# NTAG_I2C_plus_Class4_Antenna_v1.net
KiCad netlist of a schematic drawn in EAGLE
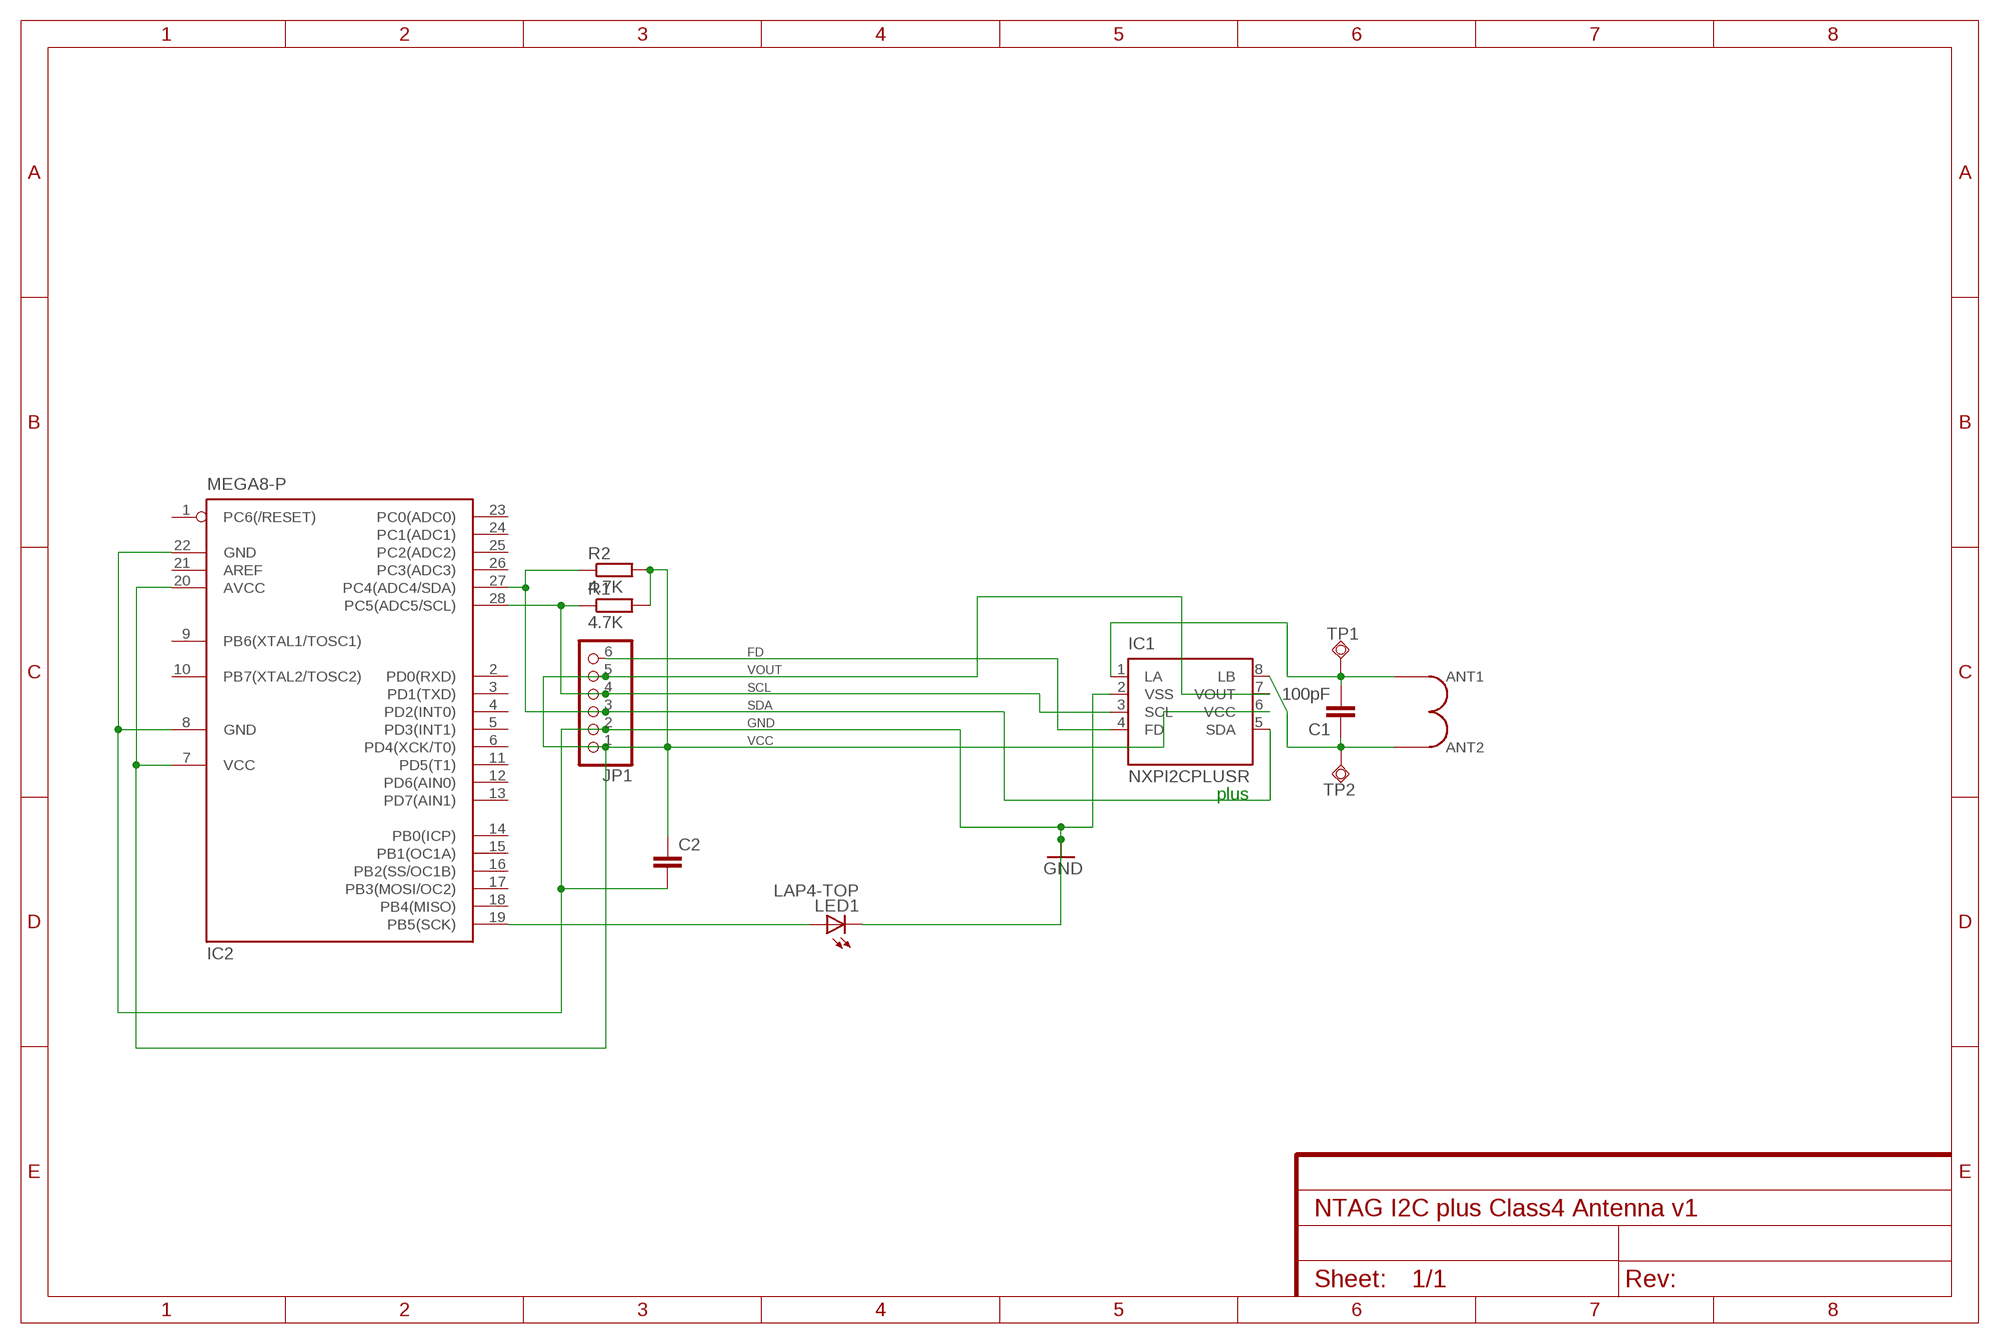
[diagram p0: schematic, sheet 1]

(export (version "E")
  (design (tool "Eeschema 10.0.6"))
  (components
    (comp (ref "C1")
      (value "100pF")
      (footprint "eagle-import:C0402K")
      (libsource (lib "eagle-import") (part "C-EUC0402K"))
    )
    (comp (ref "C2")
      (value "C-EU025-030X050")
      (footprint "eagle-import:C025-030X050")
      (libsource (lib "eagle-import") (part "rcl_334_C-EU025-030X050"))
    )
    (comp (ref "IC1")
      (value "NXPI2CPLUSR")
      (footprint "eagle-import:SO8")
      (fields (field (name "MPN") "AD780BRZ-REEL"))
      (libsource (lib "eagle-import") (part "NXPI2CPLUSR"))
    )
    (comp (ref "IC2")
      (value "MEGA8-P")
      (footprint "eagle-import:DIL28-3")
      (libsource (lib "eagle-import") (part "MEGA8-P"))
    )
    (comp (ref "JP1")
      (value "PINHD-1X6/90")
      (footprint "eagle-import:1X06_90")
      (libsource (lib "eagle-import") (part "PINHD-1X6/90"))
    )
    (comp (ref "LED1")
      (value "LAP4-TOP")
      (footprint "eagle-import:P47F-TOP")
      (libsource (lib "eagle-import") (part "P4-TOPLA"))
    )
    (comp (ref "R1")
      (value "4.7K")
      (footprint "eagle-import:0204_7")
      (libsource (lib "eagle-import") (part "R-EU_0204/7"))
    )
    (comp (ref "R2")
      (value "4.7K")
      (footprint "eagle-import:0204_7")
      (libsource (lib "eagle-import") (part "R-EU_0204/7"))
    )
    (comp (ref "TP1")
      (value "TPSQPAD1-13")
      (footprint "eagle-import:P1-13")
      (libsource (lib "eagle-import") (part "TPSQPAD1-13"))
    )
    (comp (ref "TP2")
      (value "TPSQPAD1-13")
      (footprint "eagle-import:P1-13")
      (libsource (lib "eagle-import") (part "TPSQPAD1-13"))
    )
    (comp (ref "U$1")
      (value "ENERGY-HARVESTING_3-TURNS54X27_3TURN_THIN")
      (footprint "eagle-import:54X27_3TURNS_THIN")
      (libsource (lib "eagle-import") (part "ENERGY-HARVESTING_3-TURNS54X27_3TURN_THIN"))
    )
  )
  (nets
    (net (code "1") (name "GND") (class "Default")
      (node (ref "C2") (pin "2") (pinfunction "2_2") (pintype "passive"))
      (node (ref "IC1") (pin "2") (pinfunction "VSS_2") (pintype "power_in"))
      (node (ref "IC2") (pin "22") (pinfunction "GND_22") (pintype "power_in"))
      (node (ref "IC2") (pin "8") (pinfunction "GND_8") (pintype "power_in"))
      (node (ref "JP1") (pin "2") (pinfunction "2_2") (pintype "passive"))
      (node (ref "LED1") (pin "C") (pinfunction "C_C") (pintype "passive"))
    )
    (net (code "2") (name "Net-(IC1-FD)") (class "Default")
      (node (ref "IC1") (pin "4") (pinfunction "FD_4") (pintype "bidirectional"))
      (node (ref "JP1") (pin "6") (pinfunction "6_6") (pintype "passive"))
    )
    (net (code "3") (name "Net-(IC1-LA)") (class "Default")
      (node (ref "C1") (pin "2") (pinfunction "2_2") (pintype "passive"))
      (node (ref "IC1") (pin "1") (pinfunction "LA_1") (pintype "bidirectional"))
      (node (ref "TP1") (pin "TP") (pinfunction "TP_TP") (pintype "input"))
      (node (ref "U$1") (pin "ANT1") (pinfunction "ANT1_ANT1") (pintype "bidirectional"))
    )
    (net (code "4") (name "Net-(IC1-LB)") (class "Default")
      (node (ref "C1") (pin "1") (pinfunction "1_1") (pintype "passive"))
      (node (ref "IC1") (pin "8") (pinfunction "LB_8") (pintype "bidirectional"))
      (node (ref "TP2") (pin "TP") (pinfunction "TP_TP") (pintype "input"))
      (node (ref "U$1") (pin "ANT2") (pinfunction "ANT2_ANT2") (pintype "bidirectional"))
    )
    (net (code "5") (name "Net-(IC1-SCL)") (class "Default")
      (node (ref "IC1") (pin "3") (pinfunction "SCL_3") (pintype "bidirectional"))
      (node (ref "IC2") (pin "28") (pinfunction "PC5(ADC5/SCL)_28") (pintype "bidirectional"))
      (node (ref "JP1") (pin "4") (pinfunction "4_4") (pintype "passive"))
      (node (ref "R1") (pin "1") (pinfunction "1_1") (pintype "passive"))
    )
    (net (code "6") (name "Net-(IC1-SDA)") (class "Default")
      (node (ref "IC1") (pin "5") (pinfunction "SDA_5") (pintype "bidirectional"))
      (node (ref "IC2") (pin "27") (pinfunction "PC4(ADC4/SDA)_27") (pintype "bidirectional"))
      (node (ref "JP1") (pin "3") (pinfunction "3_3") (pintype "passive"))
      (node (ref "R2") (pin "1") (pinfunction "1_1") (pintype "passive"))
    )
    (net (code "7") (name "Net-(IC1-VCC)") (class "Default")
      (node (ref "C2") (pin "1") (pinfunction "1_1") (pintype "passive"))
      (node (ref "IC1") (pin "6") (pinfunction "VCC_6") (pintype "power_in"))
      (node (ref "IC1") (pin "7") (pinfunction "VOUT_7") (pintype "power_in"))
      (node (ref "IC2") (pin "20") (pinfunction "AVCC_20") (pintype "power_in"))
      (node (ref "IC2") (pin "7") (pinfunction "VCC_7") (pintype "power_in"))
      (node (ref "JP1") (pin "1") (pinfunction "1_1") (pintype "passive"))
      (node (ref "JP1") (pin "5") (pinfunction "5_5") (pintype "passive"))
      (node (ref "R1") (pin "2") (pinfunction "2_2") (pintype "passive"))
      (node (ref "R2") (pin "2") (pinfunction "2_2") (pintype "passive"))
    )
    (net (code "8") (name "Net-(IC2-PB5(SCK))") (class "Default")
      (node (ref "IC2") (pin "19") (pinfunction "PB5(SCK)_19") (pintype "bidirectional"))
      (node (ref "LED1") (pin "A") (pinfunction "A_A") (pintype "passive"))
    )
    (net (code "9") (name "unconnected-(IC2-AREF-Pad21)") (class "Default")
      (node (ref "IC2") (pin "21") (pinfunction "AREF_21") (pintype "passive"))
    )
    (net (code "10") (name "unconnected-(IC2-PB0(ICP)-Pad14)") (class "Default")
      (node (ref "IC2") (pin "14") (pinfunction "PB0(ICP)_14") (pintype "bidirectional"))
    )
    (net (code "11") (name "unconnected-(IC2-PB1(OC1A)-Pad15)") (class "Default")
      (node (ref "IC2") (pin "15") (pinfunction "PB1(OC1A)_15") (pintype "bidirectional"))
    )
    (net (code "12") (name "unconnected-(IC2-PB2(SS{slash}OC1B)-Pad16)") (class "Default")
      (node (ref "IC2") (pin "16") (pinfunction "PB2(SS/OC1B)_16") (pintype "bidirectional"))
    )
    (net (code "13") (name "unconnected-(IC2-PB3(MOSI{slash}OC2)-Pad17)") (class "Default")
      (node (ref "IC2") (pin "17") (pinfunction "PB3(MOSI/OC2)_17") (pintype "bidirectional"))
    )
    (net (code "14") (name "unconnected-(IC2-PB4(MISO)-Pad18)") (class "Default")
      (node (ref "IC2") (pin "18") (pinfunction "PB4(MISO)_18") (pintype "bidirectional"))
    )
    (net (code "15") (name "unconnected-(IC2-PB6(XTAL1{slash}TOSC1)-Pad9)") (class "Default")
      (node (ref "IC2") (pin "9") (pinfunction "PB6(XTAL1/TOSC1)_9") (pintype "bidirectional"))
    )
    (net (code "16") (name "unconnected-(IC2-PB7(XTAL2{slash}TOSC2)-Pad10)") (class "Default")
      (node (ref "IC2") (pin "10") (pinfunction "PB7(XTAL2/TOSC2)_10") (pintype "bidirectional"))
    )
    (net (code "17") (name "unconnected-(IC2-PC0(ADC0)-Pad23)") (class "Default")
      (node (ref "IC2") (pin "23") (pinfunction "PC0(ADC0)_23") (pintype "bidirectional"))
    )
    (net (code "18") (name "unconnected-(IC2-PC1(ADC1)-Pad24)") (class "Default")
      (node (ref "IC2") (pin "24") (pinfunction "PC1(ADC1)_24") (pintype "bidirectional"))
    )
    (net (code "19") (name "unconnected-(IC2-PC2(ADC2)-Pad25)") (class "Default")
      (node (ref "IC2") (pin "25") (pinfunction "PC2(ADC2)_25") (pintype "bidirectional"))
    )
    (net (code "20") (name "unconnected-(IC2-PC3(ADC3)-Pad26)") (class "Default")
      (node (ref "IC2") (pin "26") (pinfunction "PC3(ADC3)_26") (pintype "bidirectional"))
    )
    (net (code "21") (name "unconnected-(IC2-PC6({slash}RESET)-Pad1)") (class "Default")
      (node (ref "IC2") (pin "1") (pinfunction "PC6(/RESET)_1") (pintype "bidirectional"))
    )
    (net (code "22") (name "unconnected-(IC2-PD0(RXD)-Pad2)") (class "Default")
      (node (ref "IC2") (pin "2") (pinfunction "PD0(RXD)_2") (pintype "bidirectional"))
    )
    (net (code "23") (name "unconnected-(IC2-PD1(TXD)-Pad3)") (class "Default")
      (node (ref "IC2") (pin "3") (pinfunction "PD1(TXD)_3") (pintype "bidirectional"))
    )
    (net (code "24") (name "unconnected-(IC2-PD2(INT0)-Pad4)") (class "Default")
      (node (ref "IC2") (pin "4") (pinfunction "PD2(INT0)_4") (pintype "bidirectional"))
    )
    (net (code "25") (name "unconnected-(IC2-PD3(INT1)-Pad5)") (class "Default")
      (node (ref "IC2") (pin "5") (pinfunction "PD3(INT1)_5") (pintype "bidirectional"))
    )
    (net (code "26") (name "unconnected-(IC2-PD4(XCK{slash}T0)-Pad6)") (class "Default")
      (node (ref "IC2") (pin "6") (pinfunction "PD4(XCK/T0)_6") (pintype "bidirectional"))
    )
    (net (code "27") (name "unconnected-(IC2-PD5(T1)-Pad11)") (class "Default")
      (node (ref "IC2") (pin "11") (pinfunction "PD5(T1)_11") (pintype "bidirectional"))
    )
    (net (code "28") (name "unconnected-(IC2-PD6(AIN0)-Pad12)") (class "Default")
      (node (ref "IC2") (pin "12") (pinfunction "PD6(AIN0)_12") (pintype "bidirectional"))
    )
    (net (code "29") (name "unconnected-(IC2-PD7(AIN1)-Pad13)") (class "Default")
      (node (ref "IC2") (pin "13") (pinfunction "PD7(AIN1)_13") (pintype "bidirectional"))
    )
  )
)
